# Status_Board.net
KiCad netlist of a schematic drawn in EAGLE
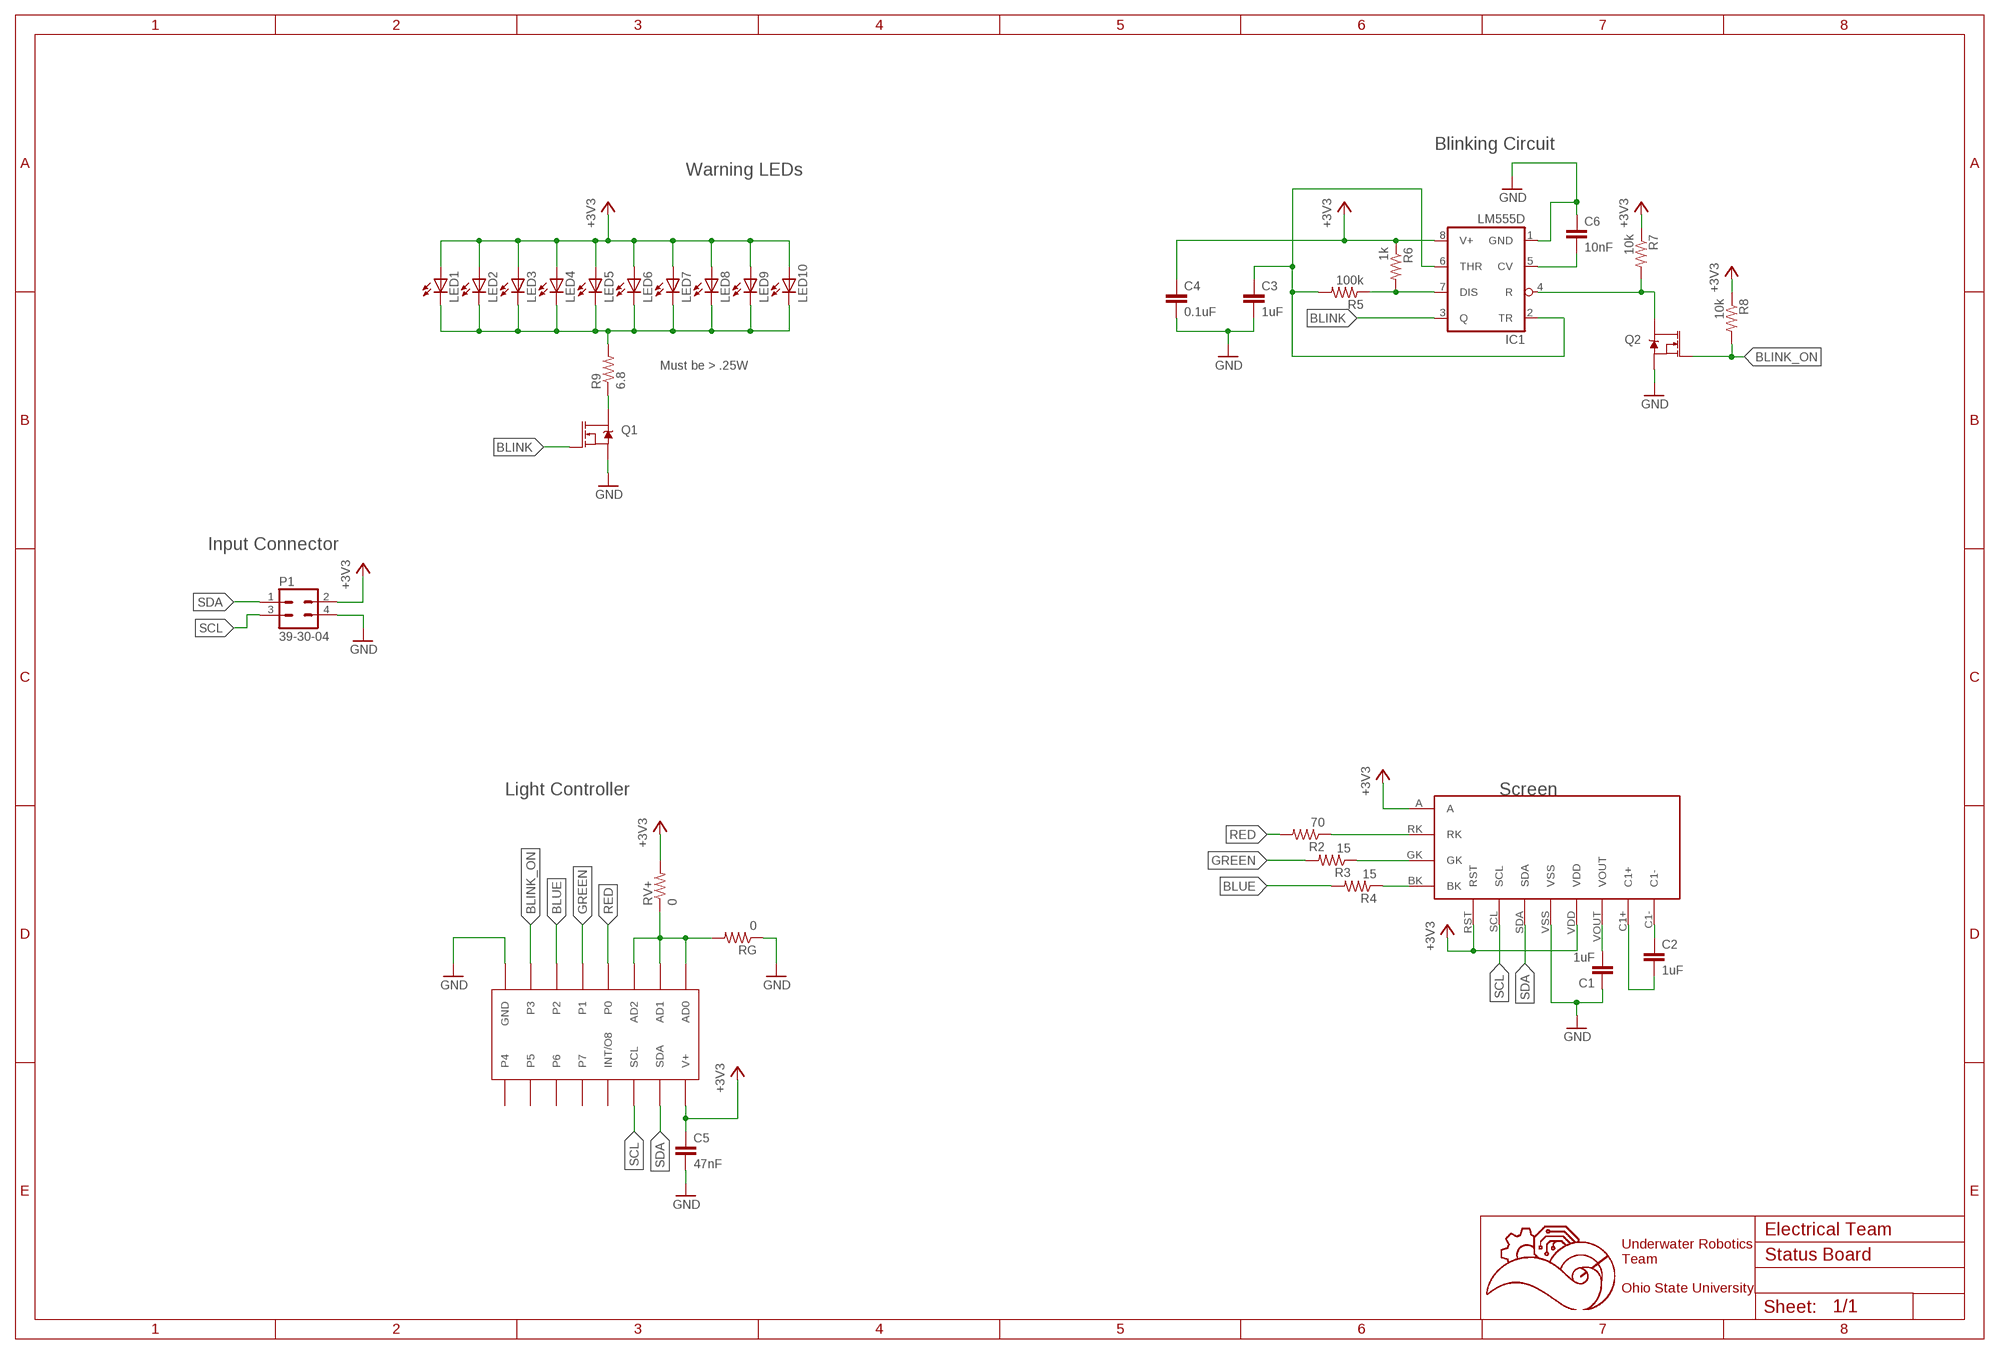
[diagram p0: schematic, sheet 1]

(export (version "E")
  (design (tool "Eeschema 10.0.6"))
  (components
    (comp (ref "C1")
      (value "1uF")
      (footprint "eagle-import:C0603")
      (libsource (lib "eagle-import") (part "C-EUC0603"))
    )
    (comp (ref "C2")
      (value "1uF")
      (footprint "eagle-import:C0603")
      (libsource (lib "eagle-import") (part "C-EUC0603"))
    )
    (comp (ref "C3")
      (value "1uF")
      (footprint "eagle-import:C0603")
      (libsource (lib "eagle-import") (part "C-EUC0603"))
    )
    (comp (ref "C4")
      (value "0.1uF")
      (footprint "eagle-import:C0603")
      (libsource (lib "eagle-import") (part "C-EUC0603"))
    )
    (comp (ref "C5")
      (value "47nF")
      (footprint "eagle-import:C0603")
      (libsource (lib "eagle-import") (part "C-EUC0603"))
    )
    (comp (ref "C6")
      (value "10nF")
      (footprint "eagle-import:C0603")
      (libsource (lib "eagle-import") (part "C-EUC0603"))
    )
    (comp (ref "IC1")
      (value "LM555D")
      (footprint "eagle-import:SO08")
      (libsource (lib "eagle-import") (part "555DLM"))
    )
    (comp (ref "LED1")
      (value "LEDCHIPLED_0603")
      (footprint "eagle-import:CHIPLED_0603")
      (libsource (lib "eagle-import") (part "LEDCHIPLED_0603"))
    )
    (comp (ref "LED2")
      (value "LEDCHIPLED_0603")
      (footprint "eagle-import:CHIPLED_0603")
      (libsource (lib "eagle-import") (part "LEDCHIPLED_0603"))
    )
    (comp (ref "LED3")
      (value "LEDCHIPLED_0603")
      (footprint "eagle-import:CHIPLED_0603")
      (libsource (lib "eagle-import") (part "LEDCHIPLED_0603"))
    )
    (comp (ref "LED4")
      (value "LEDCHIPLED_0603")
      (footprint "eagle-import:CHIPLED_0603")
      (libsource (lib "eagle-import") (part "LEDCHIPLED_0603"))
    )
    (comp (ref "LED5")
      (value "LEDCHIPLED_0603")
      (footprint "eagle-import:CHIPLED_0603")
      (libsource (lib "eagle-import") (part "LEDCHIPLED_0603"))
    )
    (comp (ref "LED6")
      (value "LEDCHIPLED_0603")
      (footprint "eagle-import:CHIPLED_0603")
      (libsource (lib "eagle-import") (part "LEDCHIPLED_0603"))
    )
    (comp (ref "LED7")
      (value "LEDCHIPLED_0603")
      (footprint "eagle-import:CHIPLED_0603")
      (libsource (lib "eagle-import") (part "LEDCHIPLED_0603"))
    )
    (comp (ref "LED8")
      (value "LEDCHIPLED_0603")
      (footprint "eagle-import:CHIPLED_0603")
      (libsource (lib "eagle-import") (part "LEDCHIPLED_0603"))
    )
    (comp (ref "LED9")
      (value "LEDCHIPLED_0603")
      (footprint "eagle-import:CHIPLED_0603")
      (libsource (lib "eagle-import") (part "LEDCHIPLED_0603"))
    )
    (comp (ref "LED10")
      (value "LEDCHIPLED_0603")
      (footprint "eagle-import:CHIPLED_0603")
      (libsource (lib "eagle-import") (part "LEDCHIPLED_0603"))
    )
    (comp (ref "P1")
      (value "39-30-04")
      (footprint "eagle-import:39-30-_04_")
      (libsource (lib "eagle-import") (part "39-30-?04?"))
    )
    (comp (ref "Q1")
      (value "310mA/60V/1.6Ω")
      (footprint "eagle-import:SOT323")
      (libsource (lib "eagle-import") (part "MOSFET-NCH-2N7002PW"))
    )
    (comp (ref "Q2")
      (value "310mA/60V/1.6Ω")
      (footprint "eagle-import:SOT323")
      (libsource (lib "eagle-import") (part "MOSFET-NCH-2N7002PW"))
    )
    (comp (ref "R2")
      (value "70")
      (footprint "eagle-import:R0603")
      (libsource (lib "eagle-import") (part "R-US_R0603"))
    )
    (comp (ref "R3")
      (value "15")
      (footprint "eagle-import:R0603")
      (libsource (lib "eagle-import") (part "R-US_R0603"))
    )
    (comp (ref "R4")
      (value "15")
      (footprint "eagle-import:R0603")
      (libsource (lib "eagle-import") (part "R-US_R0603"))
    )
    (comp (ref "R5")
      (value "100k")
      (footprint "eagle-import:R0603")
      (libsource (lib "eagle-import") (part "R-US_R0603"))
    )
    (comp (ref "R6")
      (value "1k")
      (footprint "eagle-import:R0603")
      (libsource (lib "eagle-import") (part "R-US_R0603"))
    )
    (comp (ref "R7")
      (value "10k")
      (footprint "eagle-import:R0603")
      (libsource (lib "eagle-import") (part "R-US_R0603"))
    )
    (comp (ref "R8")
      (value "10k")
      (footprint "eagle-import:R0603")
      (libsource (lib "eagle-import") (part "R-US_R0603"))
    )
    (comp (ref "R9")
      (value "6.8")
      (footprint "eagle-import:R0603")
      (libsource (lib "eagle-import") (part "R-US_R0603"))
    )
    (comp (ref "RG")
      (value "0")
      (footprint "eagle-import:R0603")
      (libsource (lib "eagle-import") (part "R-US_R0603"))
    )
    (comp (ref "RV+")
      (value "0")
      (footprint "eagle-import:R0603")
      (libsource (lib "eagle-import") (part "R-US_R0603"))
    )
    (comp (ref "U$1")
      (value "NHD-C0220BIZ")
      (footprint "eagle-import:NHD-C0220BIZ")
      (libsource (lib "eagle-import") (part "NHD-C0220BIZ"))
    )
    (comp (ref "U$2")
      (value "MAX7315")
      (footprint "eagle-import:TSSOP-16")
      (libsource (lib "eagle-import") (part "MAX7315"))
    )
  )
  (nets
    (net (code "1") (name "+3V3") (class "Default")
      (node (ref "C4") (pin "1") (pinfunction "1_1") (pintype "passive"))
      (node (ref "C5") (pin "1") (pinfunction "1_1") (pintype "passive"))
      (node (ref "IC1") (pin "8") (pinfunction "V+_8") (pintype "power_in"))
      (node (ref "LED1") (pin "A") (pinfunction "A_A") (pintype "passive"))
      (node (ref "LED10") (pin "A") (pinfunction "A_A") (pintype "passive"))
      (node (ref "LED2") (pin "A") (pinfunction "A_A") (pintype "passive"))
      (node (ref "LED3") (pin "A") (pinfunction "A_A") (pintype "passive"))
      (node (ref "LED4") (pin "A") (pinfunction "A_A") (pintype "passive"))
      (node (ref "LED5") (pin "A") (pinfunction "A_A") (pintype "passive"))
      (node (ref "LED6") (pin "A") (pinfunction "A_A") (pintype "passive"))
      (node (ref "LED7") (pin "A") (pinfunction "A_A") (pintype "passive"))
      (node (ref "LED8") (pin "A") (pinfunction "A_A") (pintype "passive"))
      (node (ref "LED9") (pin "A") (pinfunction "A_A") (pintype "passive"))
      (node (ref "P1") (pin "2") (pinfunction "2_2") (pintype "passive"))
      (node (ref "R6") (pin "1") (pinfunction "1_1") (pintype "passive"))
      (node (ref "R7") (pin "1") (pinfunction "1_1") (pintype "passive"))
      (node (ref "R8") (pin "1") (pinfunction "1_1") (pintype "passive"))
      (node (ref "RV+") (pin "2") (pinfunction "2_2") (pintype "passive"))
      (node (ref "U$1") (pin "A") (pinfunction "A_A") (pintype "bidirectional"))
      (node (ref "U$1") (pin "RST") (pinfunction "RST_RST") (pintype "bidirectional"))
      (node (ref "U$1") (pin "VDD") (pinfunction "VDD_VDD") (pintype "bidirectional"))
      (node (ref "U$2") (pin "16") (pinfunction "V+_16") (pintype "bidirectional"))
    )
    (net (code "2") (name "BLINK") (class "Default")
      (node (ref "IC1") (pin "3") (pinfunction "Q_3") (pintype "output"))
      (node (ref "Q1") (pin "1") (pinfunction "G_1") (pintype "bidirectional"))
    )
    (net (code "3") (name "BLINK_ON") (class "Default")
      (node (ref "Q2") (pin "1") (pinfunction "G_1") (pintype "bidirectional"))
      (node (ref "R8") (pin "2") (pinfunction "2_2") (pintype "passive"))
      (node (ref "U$2") (pin "7") (pinfunction "P3_7") (pintype "bidirectional"))
    )
    (net (code "4") (name "BLUE") (class "Default")
      (node (ref "R4") (pin "2") (pinfunction "2_2") (pintype "passive"))
      (node (ref "U$2") (pin "6") (pinfunction "P2_6") (pintype "bidirectional"))
    )
    (net (code "5") (name "GND") (class "Default")
      (node (ref "C1") (pin "1") (pinfunction "1_1") (pintype "passive"))
      (node (ref "C3") (pin "2") (pinfunction "2_2") (pintype "passive"))
      (node (ref "C4") (pin "2") (pinfunction "2_2") (pintype "passive"))
      (node (ref "C5") (pin "2") (pinfunction "2_2") (pintype "passive"))
      (node (ref "C6") (pin "1") (pinfunction "1_1") (pintype "passive"))
      (node (ref "IC1") (pin "1") (pinfunction "GND_1") (pintype "power_in"))
      (node (ref "P1") (pin "4") (pinfunction "4_4") (pintype "passive"))
      (node (ref "Q1") (pin "2") (pinfunction "S_2") (pintype "bidirectional"))
      (node (ref "Q2") (pin "2") (pinfunction "S_2") (pintype "bidirectional"))
      (node (ref "RG") (pin "1") (pinfunction "1_1") (pintype "passive"))
      (node (ref "U$1") (pin "VSS") (pinfunction "VSS_VSS") (pintype "bidirectional"))
      (node (ref "U$2") (pin "8") (pinfunction "GND_8") (pintype "bidirectional"))
    )
    (net (code "6") (name "GREEN") (class "Default")
      (node (ref "R3") (pin "2") (pinfunction "2_2") (pintype "passive"))
      (node (ref "U$2") (pin "5") (pinfunction "P1_5") (pintype "bidirectional"))
    )
    (net (code "7") (name "Net-(C1-Pad2)") (class "Default")
      (node (ref "C1") (pin "2") (pinfunction "2_2") (pintype "passive"))
      (node (ref "U$1") (pin "VOUT") (pinfunction "VOUT_VOUT") (pintype "bidirectional"))
    )
    (net (code "8") (name "Net-(C2-Pad1)") (class "Default")
      (node (ref "C2") (pin "1") (pinfunction "1_1") (pintype "passive"))
      (node (ref "U$1") (pin "C1-") (pinfunction "C1-_C1-") (pintype "bidirectional"))
    )
    (net (code "9") (name "Net-(C2-Pad2)") (class "Default")
      (node (ref "C2") (pin "2") (pinfunction "2_2") (pintype "passive"))
      (node (ref "U$1") (pin "C1+") (pinfunction "C1+_C1+") (pintype "bidirectional"))
    )
    (net (code "10") (name "Net-(IC1-CV)") (class "Default")
      (node (ref "C6") (pin "2") (pinfunction "2_2") (pintype "passive"))
      (node (ref "IC1") (pin "5") (pinfunction "CV_5") (pintype "input"))
    )
    (net (code "11") (name "Net-(IC1-DIS)") (class "Default")
      (node (ref "IC1") (pin "7") (pinfunction "DIS_7") (pintype "input"))
      (node (ref "R5") (pin "1") (pinfunction "1_1") (pintype "passive"))
      (node (ref "R6") (pin "2") (pinfunction "2_2") (pintype "passive"))
    )
    (net (code "12") (name "Net-(IC1-R)") (class "Default")
      (node (ref "IC1") (pin "4") (pinfunction "R_4") (pintype "input"))
      (node (ref "Q2") (pin "3") (pinfunction "D_3") (pintype "bidirectional"))
      (node (ref "R7") (pin "2") (pinfunction "2_2") (pintype "passive"))
    )
    (net (code "13") (name "Net-(IC1-THR)") (class "Default")
      (node (ref "C3") (pin "1") (pinfunction "1_1") (pintype "passive"))
      (node (ref "IC1") (pin "2") (pinfunction "TR_2") (pintype "input"))
      (node (ref "IC1") (pin "6") (pinfunction "THR_6") (pintype "input"))
      (node (ref "R5") (pin "2") (pinfunction "2_2") (pintype "passive"))
    )
    (net (code "14") (name "Net-(LED1-PadC)") (class "Default")
      (node (ref "LED1") (pin "C") (pinfunction "C_C") (pintype "passive"))
      (node (ref "LED10") (pin "C") (pinfunction "C_C") (pintype "passive"))
      (node (ref "LED2") (pin "C") (pinfunction "C_C") (pintype "passive"))
      (node (ref "LED3") (pin "C") (pinfunction "C_C") (pintype "passive"))
      (node (ref "LED4") (pin "C") (pinfunction "C_C") (pintype "passive"))
      (node (ref "LED5") (pin "C") (pinfunction "C_C") (pintype "passive"))
      (node (ref "LED6") (pin "C") (pinfunction "C_C") (pintype "passive"))
      (node (ref "LED7") (pin "C") (pinfunction "C_C") (pintype "passive"))
      (node (ref "LED8") (pin "C") (pinfunction "C_C") (pintype "passive"))
      (node (ref "LED9") (pin "C") (pinfunction "C_C") (pintype "passive"))
      (node (ref "R9") (pin "2") (pinfunction "2_2") (pintype "passive"))
    )
    (net (code "15") (name "Net-(Q1-D)") (class "Default")
      (node (ref "Q1") (pin "3") (pinfunction "D_3") (pintype "bidirectional"))
      (node (ref "R9") (pin "1") (pinfunction "1_1") (pintype "passive"))
    )
    (net (code "16") (name "Net-(R2-Pad1)") (class "Default")
      (node (ref "R2") (pin "1") (pinfunction "1_1") (pintype "passive"))
      (node (ref "U$1") (pin "RK") (pinfunction "RK_RK") (pintype "bidirectional"))
    )
    (net (code "17") (name "Net-(R3-Pad1)") (class "Default")
      (node (ref "R3") (pin "1") (pinfunction "1_1") (pintype "passive"))
      (node (ref "U$1") (pin "GK") (pinfunction "GK_GK") (pintype "bidirectional"))
    )
    (net (code "18") (name "Net-(R4-Pad1)") (class "Default")
      (node (ref "R4") (pin "1") (pinfunction "1_1") (pintype "passive"))
      (node (ref "U$1") (pin "BK") (pinfunction "BK_BK") (pintype "bidirectional"))
    )
    (net (code "19") (name "Net-(U$2-AD0)") (class "Default")
      (node (ref "RG") (pin "2") (pinfunction "2_2") (pintype "passive"))
      (node (ref "RV+") (pin "1") (pinfunction "1_1") (pintype "passive"))
      (node (ref "U$2") (pin "1") (pinfunction "AD0_1") (pintype "bidirectional"))
      (node (ref "U$2") (pin "2") (pinfunction "AD1_2") (pintype "bidirectional"))
      (node (ref "U$2") (pin "3") (pinfunction "AD2_3") (pintype "bidirectional"))
    )
    (net (code "20") (name "RED") (class "Default")
      (node (ref "R2") (pin "2") (pinfunction "2_2") (pintype "passive"))
      (node (ref "U$2") (pin "4") (pinfunction "P0_4") (pintype "bidirectional"))
    )
    (net (code "21") (name "SCL") (class "Default")
      (node (ref "P1") (pin "3") (pinfunction "3_3") (pintype "passive"))
      (node (ref "U$1") (pin "SCL") (pinfunction "SCL_SCL") (pintype "bidirectional"))
      (node (ref "U$2") (pin "14") (pinfunction "SCL_14") (pintype "bidirectional"))
    )
    (net (code "22") (name "SDA") (class "Default")
      (node (ref "P1") (pin "1") (pinfunction "1_1") (pintype "passive"))
      (node (ref "U$1") (pin "SDA") (pinfunction "SDA_SDA") (pintype "bidirectional"))
      (node (ref "U$2") (pin "15") (pinfunction "SDA_15") (pintype "bidirectional"))
    )
    (net (code "23") (name "unconnected-(U$2-INT{slash}O8-Pad13)") (class "Default")
      (node (ref "U$2") (pin "13") (pinfunction "INT/O8_13") (pintype "bidirectional"))
    )
    (net (code "24") (name "unconnected-(U$2-P4-Pad9)") (class "Default")
      (node (ref "U$2") (pin "9") (pinfunction "P4_9") (pintype "bidirectional"))
    )
    (net (code "25") (name "unconnected-(U$2-P5-Pad10)") (class "Default")
      (node (ref "U$2") (pin "10") (pinfunction "P5_10") (pintype "bidirectional"))
    )
    (net (code "26") (name "unconnected-(U$2-P6-Pad11)") (class "Default")
      (node (ref "U$2") (pin "11") (pinfunction "P6_11") (pintype "bidirectional"))
    )
    (net (code "27") (name "unconnected-(U$2-P7-Pad12)") (class "Default")
      (node (ref "U$2") (pin "12") (pinfunction "P7_12") (pintype "bidirectional"))
    )
  )
)
